# ext_BME280.net
KiCad netlist of a schematic drawn in EAGLE
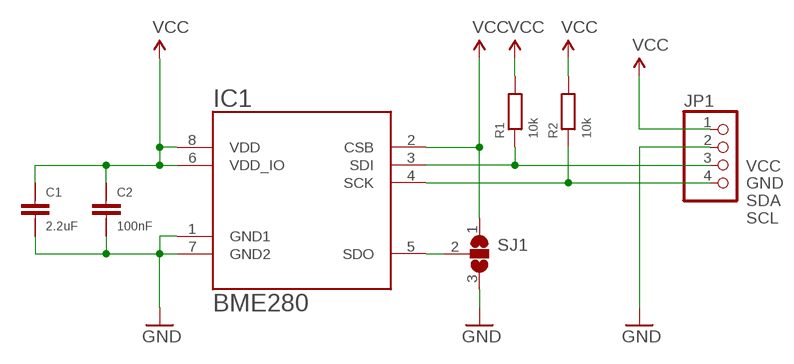
[diagram p0: schematic, sheet 1]

(export (version "E")
  (design (tool "Eeschema 10.0.6"))
  (components
    (comp (ref "C1")
      (value "2.2uF")
      (footprint "eagle-import:0402")
      (libsource (lib "eagle-import") (part "CAP-0402"))
    )
    (comp (ref "C2")
      (value "100nF")
      (footprint "eagle-import:0402")
      (libsource (lib "eagle-import") (part "CAP-0402"))
    )
    (comp (ref "IC1")
      (value "BME280")
      (footprint "eagle-import:BME280_BME280")
      (libsource (lib "eagle-import") (part "BME280_BME280"))
    )
    (comp (ref "JP1")
      (value "PINHD-1X4")
      (footprint "eagle-import:1X04")
      (libsource (lib "eagle-import") (part "PINHD-1X4"))
    )
    (comp (ref "R1")
      (value "10k")
      (footprint "eagle-import:0402")
      (libsource (lib "eagle-import") (part "RES-0402"))
    )
    (comp (ref "R2")
      (value "10k")
      (footprint "eagle-import:0402")
      (libsource (lib "eagle-import") (part "RES-0402"))
    )
    (comp (ref "SJ1")
      (value "SJ2W")
      (footprint "eagle-import:SJ_2")
      (libsource (lib "eagle-import") (part "SJ2W"))
    )
  )
  (nets
    (net (code "1") (name "GND") (class "Default")
      (node (ref "C1") (pin "P$1") (pinfunction "1_P$1") (pintype "passive"))
      (node (ref "C2") (pin "P$1") (pinfunction "1_P$1") (pintype "passive"))
      (node (ref "IC1") (pin "1") (pinfunction "GND1_1") (pintype "bidirectional"))
      (node (ref "IC1") (pin "7") (pinfunction "GND2_7") (pintype "bidirectional"))
      (node (ref "JP1") (pin "2") (pinfunction "2_2") (pintype "passive"))
      (node (ref "SJ1") (pin "3") (pinfunction "3_3") (pintype "passive"))
    )
    (net (code "2") (name "Net-(IC1-SCK)") (class "Default")
      (node (ref "IC1") (pin "4") (pinfunction "SCK_4") (pintype "bidirectional"))
      (node (ref "JP1") (pin "4") (pinfunction "4_4") (pintype "passive"))
      (node (ref "R2") (pin "P$1") (pinfunction "1_P$1") (pintype "passive"))
    )
    (net (code "3") (name "Net-(IC1-SDI)") (class "Default")
      (node (ref "IC1") (pin "3") (pinfunction "SDI_3") (pintype "bidirectional"))
      (node (ref "JP1") (pin "3") (pinfunction "3_3") (pintype "passive"))
      (node (ref "R1") (pin "P$1") (pinfunction "1_P$1") (pintype "passive"))
    )
    (net (code "4") (name "Net-(IC1-SDO)") (class "Default")
      (node (ref "IC1") (pin "5") (pinfunction "SDO_5") (pintype "bidirectional"))
      (node (ref "SJ1") (pin "2") (pinfunction "2_2") (pintype "passive"))
    )
    (net (code "5") (name "VCC") (class "Default")
      (node (ref "C1") (pin "P$2") (pinfunction "2_P$2") (pintype "passive"))
      (node (ref "C2") (pin "P$2") (pinfunction "2_P$2") (pintype "passive"))
      (node (ref "IC1") (pin "2") (pinfunction "CSB_2") (pintype "bidirectional"))
      (node (ref "IC1") (pin "6") (pinfunction "VDD_IO_6") (pintype "bidirectional"))
      (node (ref "IC1") (pin "8") (pinfunction "VDD_8") (pintype "bidirectional"))
      (node (ref "JP1") (pin "1") (pinfunction "1_1") (pintype "passive"))
      (node (ref "R1") (pin "P$2") (pinfunction "2_P$2") (pintype "passive"))
      (node (ref "R2") (pin "P$2") (pinfunction "2_P$2") (pintype "passive"))
      (node (ref "SJ1") (pin "1") (pinfunction "1_1") (pintype "passive"))
    )
  )
)
